# CableUndefinedMini_Rev2.net
KiCad netlist of a schematic drawn in EasyEDA
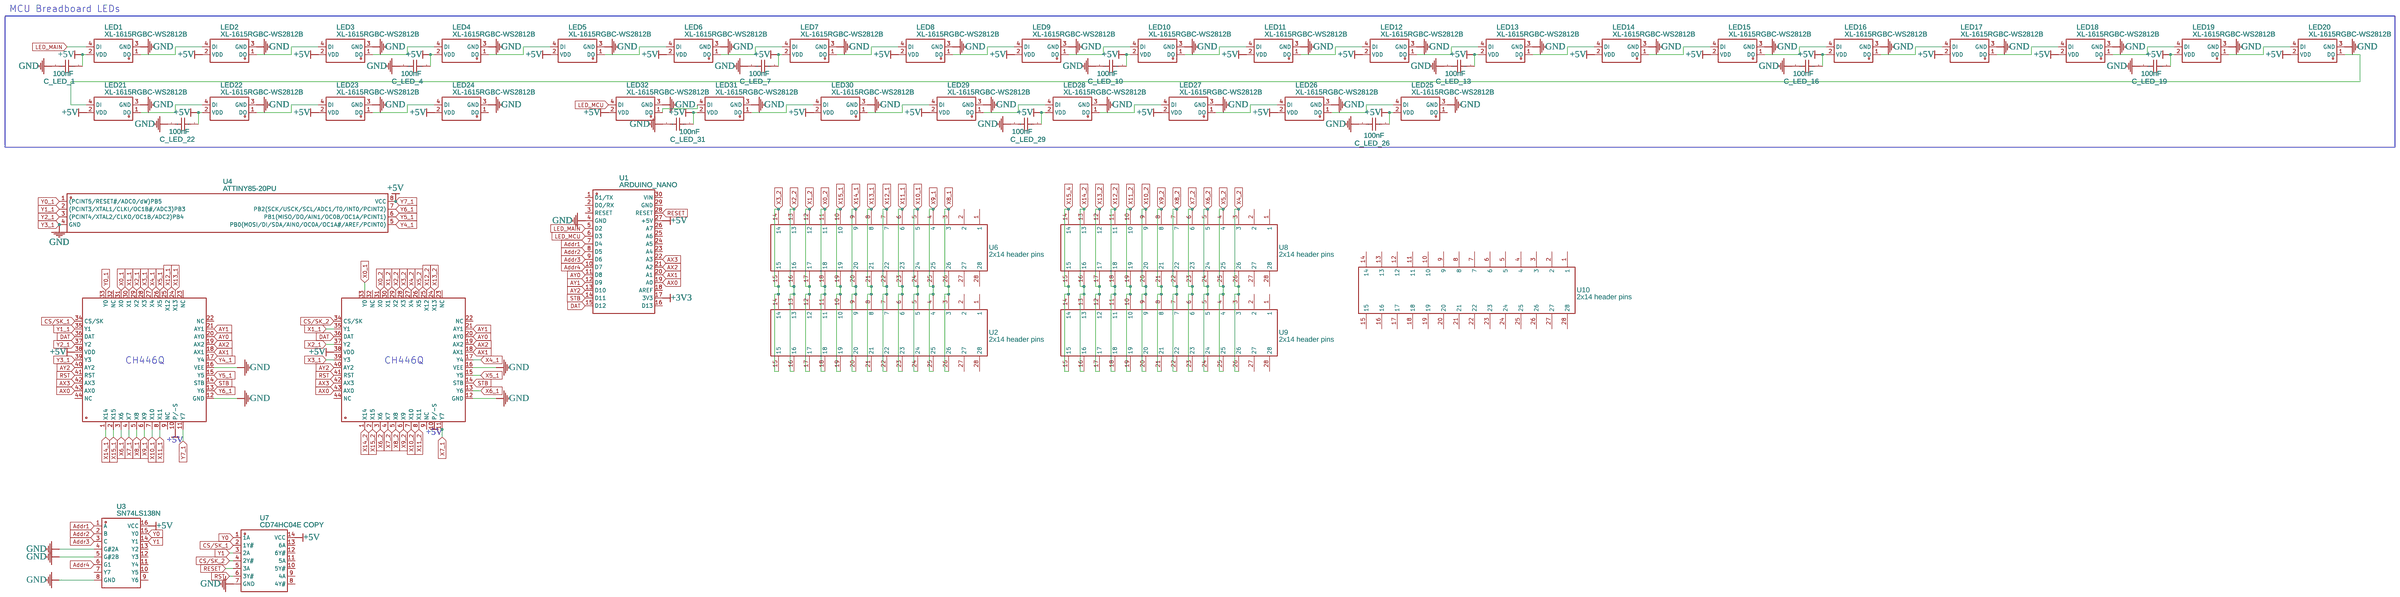
[diagram p0: schematic sheet]

(export (version "E")
  (design (tool "Eeschema 10.0.6"))
  (components
    (comp (ref "C_LED_1")
      (value "100nF")
      (fields
        (field (name "Manufacturer Part") "AC0402KRX7R9BB104")
        (field (name "Manufacturer") "YAGEO(国巨)")
      )
      (libsource (lib "") (part "AC0402KRX7R9BB104"))
    )
    (comp (ref "C_LED_4")
      (value "100nF")
      (fields
        (field (name "Manufacturer Part") "AC0402KRX7R9BB104")
        (field (name "Manufacturer") "YAGEO(国巨)")
      )
      (libsource (lib "") (part "AC0402KRX7R9BB104"))
    )
    (comp (ref "C_LED_7")
      (value "100nF")
      (fields
        (field (name "Manufacturer Part") "AC0402KRX7R9BB104")
        (field (name "Manufacturer") "YAGEO(国巨)")
      )
      (libsource (lib "") (part "AC0402KRX7R9BB104"))
    )
    (comp (ref "C_LED_10")
      (value "100nF")
      (fields
        (field (name "Manufacturer Part") "AC0402KRX7R9BB104")
        (field (name "Manufacturer") "YAGEO(国巨)")
      )
      (libsource (lib "") (part "AC0402KRX7R9BB104"))
    )
    (comp (ref "C_LED_13")
      (value "100nF")
      (fields
        (field (name "Manufacturer Part") "AC0402KRX7R9BB104")
        (field (name "Manufacturer") "YAGEO(国巨)")
      )
      (libsource (lib "") (part "AC0402KRX7R9BB104"))
    )
    (comp (ref "C_LED_16")
      (value "100nF")
      (fields
        (field (name "Manufacturer Part") "AC0402KRX7R9BB104")
        (field (name "Manufacturer") "YAGEO(国巨)")
      )
      (libsource (lib "") (part "AC0402KRX7R9BB104"))
    )
    (comp (ref "C_LED_19")
      (value "100nF")
      (fields
        (field (name "Manufacturer Part") "AC0402KRX7R9BB104")
        (field (name "Manufacturer") "YAGEO(国巨)")
      )
      (libsource (lib "") (part "AC0402KRX7R9BB104"))
    )
    (comp (ref "C_LED_22")
      (value "100nF")
      (fields
        (field (name "Manufacturer Part") "AC0402KRX7R9BB104")
        (field (name "Manufacturer") "YAGEO(国巨)")
      )
      (libsource (lib "") (part "AC0402KRX7R9BB104"))
    )
    (comp (ref "C_LED_26")
      (value "100nF")
      (fields
        (field (name "Manufacturer Part") "AC0402KRX7R9BB104")
        (field (name "Manufacturer") "YAGEO(国巨)")
      )
      (libsource (lib "") (part "AC0402KRX7R9BB104"))
    )
    (comp (ref "C_LED_29")
      (value "100nF")
      (fields
        (field (name "Manufacturer Part") "AC0402KRX7R9BB104")
        (field (name "Manufacturer") "YAGEO(国巨)")
      )
      (libsource (lib "") (part "AC0402KRX7R9BB104"))
    )
    (comp (ref "C_LED_31")
      (value "100nF")
      (fields
        (field (name "Manufacturer Part") "AC0402KRX7R9BB104")
        (field (name "Manufacturer") "YAGEO(国巨)")
      )
      (libsource (lib "") (part "AC0402KRX7R9BB104"))
    )
    (comp (ref "LED1")
      (value "XL-1615RGBC-WS2812B")
      (fields (field (name "Manufacturer") "XINGLIGHT(成兴光)"))
      (libsource (lib "") (part "XL-1615RGBC-WS2812B"))
    )
    (comp (ref "LED2")
      (value "XL-1615RGBC-WS2812B")
      (fields (field (name "Manufacturer") "XINGLIGHT(成兴光)"))
      (libsource (lib "") (part "XL-1615RGBC-WS2812B"))
    )
    (comp (ref "LED3")
      (value "XL-1615RGBC-WS2812B")
      (fields (field (name "Manufacturer") "XINGLIGHT(成兴光)"))
      (libsource (lib "") (part "XL-1615RGBC-WS2812B"))
    )
    (comp (ref "LED4")
      (value "XL-1615RGBC-WS2812B")
      (fields (field (name "Manufacturer") "XINGLIGHT(成兴光)"))
      (libsource (lib "") (part "XL-1615RGBC-WS2812B"))
    )
    (comp (ref "LED5")
      (value "XL-1615RGBC-WS2812B")
      (fields (field (name "Manufacturer") "XINGLIGHT(成兴光)"))
      (libsource (lib "") (part "XL-1615RGBC-WS2812B"))
    )
    (comp (ref "LED6")
      (value "XL-1615RGBC-WS2812B")
      (fields (field (name "Manufacturer") "XINGLIGHT(成兴光)"))
      (libsource (lib "") (part "XL-1615RGBC-WS2812B"))
    )
    (comp (ref "LED7")
      (value "XL-1615RGBC-WS2812B")
      (fields (field (name "Manufacturer") "XINGLIGHT(成兴光)"))
      (libsource (lib "") (part "XL-1615RGBC-WS2812B"))
    )
    (comp (ref "LED8")
      (value "XL-1615RGBC-WS2812B")
      (fields (field (name "Manufacturer") "XINGLIGHT(成兴光)"))
      (libsource (lib "") (part "XL-1615RGBC-WS2812B"))
    )
    (comp (ref "LED9")
      (value "XL-1615RGBC-WS2812B")
      (fields (field (name "Manufacturer") "XINGLIGHT(成兴光)"))
      (libsource (lib "") (part "XL-1615RGBC-WS2812B"))
    )
    (comp (ref "LED10")
      (value "XL-1615RGBC-WS2812B")
      (fields (field (name "Manufacturer") "XINGLIGHT(成兴光)"))
      (libsource (lib "") (part "XL-1615RGBC-WS2812B"))
    )
    (comp (ref "LED11")
      (value "XL-1615RGBC-WS2812B")
      (fields (field (name "Manufacturer") "XINGLIGHT(成兴光)"))
      (libsource (lib "") (part "XL-1615RGBC-WS2812B"))
    )
    (comp (ref "LED12")
      (value "XL-1615RGBC-WS2812B")
      (fields (field (name "Manufacturer") "XINGLIGHT(成兴光)"))
      (libsource (lib "") (part "XL-1615RGBC-WS2812B"))
    )
    (comp (ref "LED13")
      (value "XL-1615RGBC-WS2812B")
      (fields (field (name "Manufacturer") "XINGLIGHT(成兴光)"))
      (libsource (lib "") (part "XL-1615RGBC-WS2812B"))
    )
    (comp (ref "LED14")
      (value "XL-1615RGBC-WS2812B")
      (fields (field (name "Manufacturer") "XINGLIGHT(成兴光)"))
      (libsource (lib "") (part "XL-1615RGBC-WS2812B"))
    )
    (comp (ref "LED15")
      (value "XL-1615RGBC-WS2812B")
      (fields (field (name "Manufacturer") "XINGLIGHT(成兴光)"))
      (libsource (lib "") (part "XL-1615RGBC-WS2812B"))
    )
    (comp (ref "LED16")
      (value "XL-1615RGBC-WS2812B")
      (fields (field (name "Manufacturer") "XINGLIGHT(成兴光)"))
      (libsource (lib "") (part "XL-1615RGBC-WS2812B"))
    )
    (comp (ref "LED17")
      (value "XL-1615RGBC-WS2812B")
      (fields (field (name "Manufacturer") "XINGLIGHT(成兴光)"))
      (libsource (lib "") (part "XL-1615RGBC-WS2812B"))
    )
    (comp (ref "LED18")
      (value "XL-1615RGBC-WS2812B")
      (fields (field (name "Manufacturer") "XINGLIGHT(成兴光)"))
      (libsource (lib "") (part "XL-1615RGBC-WS2812B"))
    )
    (comp (ref "LED19")
      (value "XL-1615RGBC-WS2812B")
      (fields (field (name "Manufacturer") "XINGLIGHT(成兴光)"))
      (libsource (lib "") (part "XL-1615RGBC-WS2812B"))
    )
    (comp (ref "LED20")
      (value "XL-1615RGBC-WS2812B")
      (fields (field (name "Manufacturer") "XINGLIGHT(成兴光)"))
      (libsource (lib "") (part "XL-1615RGBC-WS2812B"))
    )
    (comp (ref "LED21")
      (value "XL-1615RGBC-WS2812B")
      (fields (field (name "Manufacturer") "XINGLIGHT(成兴光)"))
      (libsource (lib "") (part "XL-1615RGBC-WS2812B"))
    )
    (comp (ref "LED22")
      (value "XL-1615RGBC-WS2812B")
      (fields (field (name "Manufacturer") "XINGLIGHT(成兴光)"))
      (libsource (lib "") (part "XL-1615RGBC-WS2812B"))
    )
    (comp (ref "LED23")
      (value "XL-1615RGBC-WS2812B")
      (fields (field (name "Manufacturer") "XINGLIGHT(成兴光)"))
      (libsource (lib "") (part "XL-1615RGBC-WS2812B"))
    )
    (comp (ref "LED24")
      (value "XL-1615RGBC-WS2812B")
      (fields (field (name "Manufacturer") "XINGLIGHT(成兴光)"))
      (libsource (lib "") (part "XL-1615RGBC-WS2812B"))
    )
    (comp (ref "LED25")
      (value "XL-1615RGBC-WS2812B")
      (fields (field (name "Manufacturer") "XINGLIGHT(成兴光)"))
      (libsource (lib "") (part "XL-1615RGBC-WS2812B"))
    )
    (comp (ref "LED26")
      (value "XL-1615RGBC-WS2812B")
      (fields (field (name "Manufacturer") "XINGLIGHT(成兴光)"))
      (libsource (lib "") (part "XL-1615RGBC-WS2812B"))
    )
    (comp (ref "LED27")
      (value "XL-1615RGBC-WS2812B")
      (fields (field (name "Manufacturer") "XINGLIGHT(成兴光)"))
      (libsource (lib "") (part "XL-1615RGBC-WS2812B"))
    )
    (comp (ref "LED28")
      (value "XL-1615RGBC-WS2812B")
      (fields (field (name "Manufacturer") "XINGLIGHT(成兴光)"))
      (libsource (lib "") (part "XL-1615RGBC-WS2812B"))
    )
    (comp (ref "LED29")
      (value "XL-1615RGBC-WS2812B")
      (fields (field (name "Manufacturer") "XINGLIGHT(成兴光)"))
      (libsource (lib "") (part "XL-1615RGBC-WS2812B"))
    )
    (comp (ref "LED30")
      (value "XL-1615RGBC-WS2812B")
      (fields (field (name "Manufacturer") "XINGLIGHT(成兴光)"))
      (libsource (lib "") (part "XL-1615RGBC-WS2812B"))
    )
    (comp (ref "LED31")
      (value "XL-1615RGBC-WS2812B")
      (fields (field (name "Manufacturer") "XINGLIGHT(成兴光)"))
      (libsource (lib "") (part "XL-1615RGBC-WS2812B"))
    )
    (comp (ref "LED32")
      (value "XL-1615RGBC-WS2812B")
      (fields (field (name "Manufacturer") "XINGLIGHT(成兴光)"))
      (libsource (lib "") (part "XL-1615RGBC-WS2812B"))
    )
    (comp (ref "M1")
      (value "CH446Q")
      (fields (field (name "Manufacturer") "WCH(南京沁恒)"))
      (libsource (lib "") (part "CH446Q"))
    )
    (comp (ref "M2")
      (value "CH446Q")
      (fields (field (name "Manufacturer") "WCH(南京沁恒)"))
      (libsource (lib "") (part "CH446Q"))
    )
    (comp (ref "U1") (value "ARDUINO_NANO") (libsource (lib "") (part "ARDUINO_NANO")))
    (comp (ref "U2") (value "2x14 header pins") (libsource (lib "") (part "2x14 header pins")))
    (comp (ref "U3")
      (value "SN74LS138N")
      (fields (field (name "Manufacturer") "TI(德州仪器)"))
      (libsource (lib "") (part "SN74LS138N"))
    )
    (comp (ref "U4")
      (value "ATTINY85-20PU")
      (fields (field (name "Manufacturer") "MICROCHIP(美国微芯)"))
      (libsource (lib "") (part "ATTINY85-20PU"))
    )
    (comp (ref "U6") (value "2x14 header pins") (libsource (lib "") (part "2x14 header pins")))
    (comp (ref "U7")
      (value "CD74HC04E COPY")
      (fields
        (field (name "Manufacturer Part") "CD74HC04E")
        (field (name "Manufacturer") "Texas Instruments")
      )
      (libsource (lib "") (part "CD74HC04E COPY"))
    )
    (comp (ref "U8") (value "2x14 header pins") (libsource (lib "") (part "2x14 header pins")))
    (comp (ref "U9") (value "2x14 header pins") (libsource (lib "") (part "2x14 header pins")))
    (comp (ref "U10") (value "2x14 header pins") (libsource (lib "") (part "2x14 header pins")))
  )
  (nets
    (net (code "1") (name "+3V3") (class "Default")
      (node (ref "U1") (pin "17") (pinfunction "3V3_17") (pintype "unspecified"))
    )
    (net (code "2") (name "AX0") (class "Default")
      (node (ref "M1") (pin "43") (pinfunction "AX0_43") (pintype "unspecified"))
      (node (ref "M2") (pin "43") (pinfunction "AX0_43") (pintype "unspecified"))
      (node (ref "U1") (pin "19") (pinfunction "A0_19") (pintype "unspecified"))
    )
    (net (code "3") (name "AX1") (class "Default")
      (node (ref "M1") (pin "18") (pinfunction "AX1_18") (pintype "unspecified"))
      (node (ref "M2") (pin "18") (pinfunction "AX1_18") (pintype "unspecified"))
      (node (ref "U1") (pin "20") (pinfunction "A1_20") (pintype "unspecified"))
    )
    (net (code "4") (name "AX2") (class "Default")
      (node (ref "M1") (pin "19") (pinfunction "AX2_19") (pintype "unspecified"))
      (node (ref "M2") (pin "19") (pinfunction "AX2_19") (pintype "unspecified"))
      (node (ref "U1") (pin "21") (pinfunction "A2_21") (pintype "unspecified"))
    )
    (net (code "5") (name "AX3") (class "Default")
      (node (ref "M1") (pin "42") (pinfunction "AX3_42") (pintype "unspecified"))
      (node (ref "M2") (pin "42") (pinfunction "AX3_42") (pintype "unspecified"))
      (node (ref "U1") (pin "22") (pinfunction "A3_22") (pintype "unspecified"))
    )
    (net (code "6") (name "AY0") (class "Default")
      (node (ref "M1") (pin "20") (pinfunction "AY0_20") (pintype "unspecified"))
      (node (ref "M2") (pin "20") (pinfunction "AY0_20") (pintype "unspecified"))
      (node (ref "U1") (pin "11") (pinfunction "D8_11") (pintype "unspecified"))
    )
    (net (code "7") (name "AY1") (class "Default")
      (node (ref "M1") (pin "21") (pinfunction "AY1_21") (pintype "unspecified"))
      (node (ref "M2") (pin "21") (pinfunction "AY1_21") (pintype "unspecified"))
      (node (ref "U1") (pin "12") (pinfunction "D9_12") (pintype "unspecified"))
    )
    (net (code "8") (name "AY2") (class "Default")
      (node (ref "M1") (pin "40") (pinfunction "AY2_40") (pintype "unspecified"))
      (node (ref "M2") (pin "40") (pinfunction "AY2_40") (pintype "unspecified"))
      (node (ref "U1") (pin "13") (pinfunction "D10_13") (pintype "unspecified"))
    )
    (net (code "9") (name "Addr1") (class "Default")
      (node (ref "U1") (pin "7") (pinfunction "D4_7") (pintype "unspecified"))
      (node (ref "U3") (pin "1") (pinfunction "A_1") (pintype "unspecified"))
    )
    (net (code "10") (name "Addr2") (class "Default")
      (node (ref "U1") (pin "8") (pinfunction "D5_8") (pintype "unspecified"))
      (node (ref "U3") (pin "2") (pinfunction "B_2") (pintype "unspecified"))
    )
    (net (code "11") (name "Addr3") (class "Default")
      (node (ref "U1") (pin "9") (pinfunction "D6_9") (pintype "unspecified"))
      (node (ref "U3") (pin "3") (pinfunction "C_3") (pintype "unspecified"))
    )
    (net (code "12") (name "Addr4") (class "Default")
      (node (ref "U1") (pin "10") (pinfunction "D7_10") (pintype "unspecified"))
      (node (ref "U3") (pin "6") (pinfunction "G1_6") (pintype "unspecified"))
    )
    (net (code "13") (name "CS{slash}SK_1") (class "Default")
      (node (ref "M1") (pin "34") (pinfunction "CS/SK_34") (pintype "unspecified"))
      (node (ref "U7") (pin "2") (pinfunction "1Y#_2") (pintype "unspecified"))
    )
    (net (code "14") (name "CS{slash}SK_2") (class "Default")
      (node (ref "M2") (pin "34") (pinfunction "CS/SK_34") (pintype "unspecified"))
      (node (ref "U7") (pin "4") (pinfunction "2Y#_4") (pintype "unspecified"))
    )
    (net (code "15") (name "DAT") (class "Default")
      (node (ref "M1") (pin "36") (pinfunction "DAT_36") (pintype "unspecified"))
      (node (ref "M2") (pin "36") (pinfunction "DAT_36") (pintype "unspecified"))
      (node (ref "U1") (pin "15") (pinfunction "D12_15") (pintype "unspecified"))
    )
    (net (code "16") (name "LED_MAIN") (class "Default")
      (node (ref "LED1") (pin "4") (pinfunction "DI_4") (pintype "unspecified"))
      (node (ref "U1") (pin "5") (pinfunction "D2_5") (pintype "unspecified"))
    )
    (net (code "17") (name "LED_MCU") (class "Default")
      (node (ref "LED32") (pin "4") (pinfunction "DI_4") (pintype "unspecified"))
      (node (ref "U1") (pin "6") (pinfunction "D3_6") (pintype "unspecified"))
    )
    (net (code "18") (name "Net-(LED1-DO)") (class "Default")
      (node (ref "LED1") (pin "1") (pinfunction "DO_1") (pintype "unspecified"))
      (node (ref "LED2") (pin "4") (pinfunction "DI_4") (pintype "unspecified"))
    )
    (net (code "19") (name "Net-(LED2-DO)") (class "Default")
      (node (ref "LED2") (pin "1") (pinfunction "DO_1") (pintype "unspecified"))
      (node (ref "LED3") (pin "4") (pinfunction "DI_4") (pintype "unspecified"))
    )
    (net (code "20") (name "Net-(LED3-DO)") (class "Default")
      (node (ref "LED3") (pin "1") (pinfunction "DO_1") (pintype "unspecified"))
      (node (ref "LED4") (pin "4") (pinfunction "DI_4") (pintype "unspecified"))
    )
    (net (code "21") (name "Net-(LED4-DO)") (class "Default")
      (node (ref "LED4") (pin "1") (pinfunction "DO_1") (pintype "unspecified"))
      (node (ref "LED5") (pin "4") (pinfunction "DI_4") (pintype "unspecified"))
    )
    (net (code "22") (name "Net-(LED5-DO)") (class "Default")
      (node (ref "LED5") (pin "1") (pinfunction "DO_1") (pintype "unspecified"))
      (node (ref "LED6") (pin "4") (pinfunction "DI_4") (pintype "unspecified"))
    )
    (net (code "23") (name "Net-(LED6-DO)") (class "Default")
      (node (ref "LED6") (pin "1") (pinfunction "DO_1") (pintype "unspecified"))
      (node (ref "LED7") (pin "4") (pinfunction "DI_4") (pintype "unspecified"))
    )
    (net (code "24") (name "Net-(LED7-DO)") (class "Default")
      (node (ref "LED7") (pin "1") (pinfunction "DO_1") (pintype "unspecified"))
      (node (ref "LED8") (pin "4") (pinfunction "DI_4") (pintype "unspecified"))
    )
    (net (code "25") (name "Net-(LED8-DO)") (class "Default")
      (node (ref "LED8") (pin "1") (pinfunction "DO_1") (pintype "unspecified"))
      (node (ref "LED9") (pin "4") (pinfunction "DI_4") (pintype "unspecified"))
    )
    (net (code "26") (name "Net-(LED10-DI)") (class "Default")
      (node (ref "LED10") (pin "4") (pinfunction "DI_4") (pintype "unspecified"))
      (node (ref "LED9") (pin "1") (pinfunction "DO_1") (pintype "unspecified"))
    )
    (net (code "27") (name "Net-(LED10-DO)") (class "Default")
      (node (ref "LED10") (pin "1") (pinfunction "DO_1") (pintype "unspecified"))
      (node (ref "LED11") (pin "4") (pinfunction "DI_4") (pintype "unspecified"))
    )
    (net (code "28") (name "Net-(LED11-DO)") (class "Default")
      (node (ref "LED11") (pin "1") (pinfunction "DO_1") (pintype "unspecified"))
      (node (ref "LED12") (pin "4") (pinfunction "DI_4") (pintype "unspecified"))
    )
    (net (code "29") (name "Net-(LED12-DO)") (class "Default")
      (node (ref "LED12") (pin "1") (pinfunction "DO_1") (pintype "unspecified"))
      (node (ref "LED13") (pin "4") (pinfunction "DI_4") (pintype "unspecified"))
    )
    (net (code "30") (name "Net-(LED13-DO)") (class "Default")
      (node (ref "LED13") (pin "1") (pinfunction "DO_1") (pintype "unspecified"))
      (node (ref "LED14") (pin "4") (pinfunction "DI_4") (pintype "unspecified"))
    )
    (net (code "31") (name "Net-(LED14-DO)") (class "Default")
      (node (ref "LED14") (pin "1") (pinfunction "DO_1") (pintype "unspecified"))
      (node (ref "LED15") (pin "4") (pinfunction "DI_4") (pintype "unspecified"))
    )
    (net (code "32") (name "Net-(LED15-DO)") (class "Default")
      (node (ref "LED15") (pin "1") (pinfunction "DO_1") (pintype "unspecified"))
      (node (ref "LED16") (pin "4") (pinfunction "DI_4") (pintype "unspecified"))
    )
    (net (code "33") (name "Net-(LED16-DO)") (class "Default")
      (node (ref "LED16") (pin "1") (pinfunction "DO_1") (pintype "unspecified"))
      (node (ref "LED17") (pin "4") (pinfunction "DI_4") (pintype "unspecified"))
    )
    (net (code "34") (name "Net-(LED17-DO)") (class "Default")
      (node (ref "LED17") (pin "1") (pinfunction "DO_1") (pintype "unspecified"))
      (node (ref "LED18") (pin "4") (pinfunction "DI_4") (pintype "unspecified"))
    )
    (net (code "35") (name "Net-(LED18-DO)") (class "Default")
      (node (ref "LED18") (pin "1") (pinfunction "DO_1") (pintype "unspecified"))
      (node (ref "LED19") (pin "4") (pinfunction "DI_4") (pintype "unspecified"))
    )
    (net (code "36") (name "Net-(LED19-DO)") (class "Default")
      (node (ref "LED19") (pin "1") (pinfunction "DO_1") (pintype "unspecified"))
      (node (ref "LED20") (pin "4") (pinfunction "DI_4") (pintype "unspecified"))
    )
    (net (code "37") (name "Net-(LED20-DO)") (class "Default")
      (node (ref "LED20") (pin "1") (pinfunction "DO_1") (pintype "unspecified"))
      (node (ref "LED21") (pin "4") (pinfunction "DI_4") (pintype "unspecified"))
    )
    (net (code "38") (name "Net-(LED21-DO)") (class "Default")
      (node (ref "LED21") (pin "1") (pinfunction "DO_1") (pintype "unspecified"))
      (node (ref "LED22") (pin "4") (pinfunction "DI_4") (pintype "unspecified"))
    )
    (net (code "39") (name "Net-(LED22-DO)") (class "Default")
      (node (ref "LED22") (pin "1") (pinfunction "DO_1") (pintype "unspecified"))
      (node (ref "LED23") (pin "4") (pinfunction "DI_4") (pintype "unspecified"))
    )
    (net (code "40") (name "Net-(LED23-DO)") (class "Default")
      (node (ref "LED23") (pin "1") (pinfunction "DO_1") (pintype "unspecified"))
      (node (ref "LED24") (pin "4") (pinfunction "DI_4") (pintype "unspecified"))
    )
    (net (code "41") (name "Net-(LED25-DI)") (class "Default")
      (node (ref "LED25") (pin "4") (pinfunction "DI_4") (pintype "unspecified"))
      (node (ref "LED26") (pin "1") (pinfunction "DO_1") (pintype "unspecified"))
    )
    (net (code "42") (name "Net-(LED26-DI)") (class "Default")
      (node (ref "LED26") (pin "4") (pinfunction "DI_4") (pintype "unspecified"))
      (node (ref "LED27") (pin "1") (pinfunction "DO_1") (pintype "unspecified"))
    )
    (net (code "43") (name "Net-(LED27-DI)") (class "Default")
      (node (ref "LED27") (pin "4") (pinfunction "DI_4") (pintype "unspecified"))
      (node (ref "LED28") (pin "1") (pinfunction "DO_1") (pintype "unspecified"))
    )
    (net (code "44") (name "Net-(LED28-DI)") (class "Default")
      (node (ref "LED28") (pin "4") (pinfunction "DI_4") (pintype "unspecified"))
      (node (ref "LED29") (pin "1") (pinfunction "DO_1") (pintype "unspecified"))
    )
    (net (code "45") (name "Net-(LED29-DI)") (class "Default")
      (node (ref "LED29") (pin "4") (pinfunction "DI_4") (pintype "unspecified"))
      (node (ref "LED30") (pin "1") (pinfunction "DO_1") (pintype "unspecified"))
    )
    (net (code "46") (name "Net-(LED30-DI)") (class "Default")
      (node (ref "LED30") (pin "4") (pinfunction "DI_4") (pintype "unspecified"))
      (node (ref "LED31") (pin "1") (pinfunction "DO_1") (pintype "unspecified"))
    )
    (net (code "47") (name "Net-(LED31-DI)") (class "Default")
      (node (ref "LED31") (pin "4") (pinfunction "DI_4") (pintype "unspecified"))
      (node (ref "LED32") (pin "1") (pinfunction "DO_1") (pintype "unspecified"))
    )
    (net (code "48") (name "RESET") (class "Default")
      (node (ref "U1") (pin "28") (pinfunction "RESET_28") (pintype "unspecified"))
      (node (ref "U7") (pin "5") (pinfunction "3A_5") (pintype "unspecified"))
    )
    (net (code "49") (name "RST") (class "Default")
      (node (ref "M1") (pin "41") (pinfunction "RST_41") (pintype "unspecified"))
      (node (ref "M2") (pin "41") (pinfunction "RST_41") (pintype "unspecified"))
      (node (ref "U7") (pin "6") (pinfunction "3Y#_6") (pintype "unspecified"))
    )
    (net (code "50") (name "STB") (class "Default")
      (node (ref "M1") (pin "14") (pinfunction "STB_14") (pintype "unspecified"))
      (node (ref "M2") (pin "14") (pinfunction "STB_14") (pintype "unspecified"))
      (node (ref "U1") (pin "14") (pinfunction "D11_14") (pintype "unspecified"))
    )
    (net (code "51") (name "X0_1") (class "Default")
      (node (ref "M1") (pin "31") (pinfunction "X0_31") (pintype "unspecified"))
      (node (ref "M2") (pin "33") (pinfunction "Y0_33") (pintype "unspecified"))
    )
    (net (code "52") (name "X0_2") (class "Default")
      (node (ref "M2") (pin "31") (pinfunction "X0_31") (pintype "unspecified"))
      (node (ref "U2") (pin "11") (pinfunction "11_11") (pintype "unspecified"))
      (node (ref "U2") (pin "18") (pinfunction "18_18") (pintype "unspecified"))
      (node (ref "U6") (pin "11") (pinfunction "11_11") (pintype "unspecified"))
      (node (ref "U6") (pin "18") (pinfunction "18_18") (pintype "unspecified"))
    )
    (net (code "53") (name "X1_1") (class "Default")
      (node (ref "M1") (pin "30") (pinfunction "X1_30") (pintype "unspecified"))
      (node (ref "M2") (pin "35") (pinfunction "Y1_35") (pintype "unspecified"))
    )
    (net (code "54") (name "X1_2") (class "Default")
      (node (ref "M2") (pin "30") (pinfunction "X1_30") (pintype "unspecified"))
      (node (ref "U2") (pin "12") (pinfunction "12_12") (pintype "unspecified"))
      (node (ref "U2") (pin "17") (pinfunction "17_17") (pintype "unspecified"))
      (node (ref "U6") (pin "12") (pinfunction "12_12") (pintype "unspecified"))
      (node (ref "U6") (pin "17") (pinfunction "17_17") (pintype "unspecified"))
    )
    (net (code "55") (name "X2_1") (class "Default")
      (node (ref "M1") (pin "29") (pinfunction "X2_29") (pintype "unspecified"))
      (node (ref "M2") (pin "37") (pinfunction "Y2_37") (pintype "unspecified"))
    )
    (net (code "56") (name "X2_2") (class "Default")
      (node (ref "M2") (pin "29") (pinfunction "X2_29") (pintype "unspecified"))
      (node (ref "U2") (pin "13") (pinfunction "13_13") (pintype "unspecified"))
      (node (ref "U2") (pin "16") (pinfunction "16_16") (pintype "unspecified"))
      (node (ref "U6") (pin "13") (pinfunction "13_13") (pintype "unspecified"))
      (node (ref "U6") (pin "16") (pinfunction "16_16") (pintype "unspecified"))
    )
    (net (code "57") (name "X3_1") (class "Default")
      (node (ref "M1") (pin "28") (pinfunction "X3_28") (pintype "unspecified"))
      (node (ref "M2") (pin "39") (pinfunction "Y3_39") (pintype "unspecified"))
    )
    (net (code "58") (name "X3_2") (class "Default")
      (node (ref "M2") (pin "28") (pinfunction "X3_28") (pintype "unspecified"))
      (node (ref "U2") (pin "14") (pinfunction "14_14") (pintype "unspecified"))
      (node (ref "U2") (pin "15") (pinfunction "15_15") (pintype "unspecified"))
      (node (ref "U6") (pin "14") (pinfunction "14_14") (pintype "unspecified"))
      (node (ref "U6") (pin "15") (pinfunction "15_15") (pintype "unspecified"))
    )
    (net (code "59") (name "X4_1") (class "Default")
      (node (ref "M1") (pin "27") (pinfunction "X4_27") (pintype "unspecified"))
      (node (ref "M2") (pin "17") (pinfunction "Y4_17") (pintype "unspecified"))
    )
    (net (code "60") (name "X4_2") (class "Default")
      (node (ref "M2") (pin "27") (pinfunction "X4_27") (pintype "unspecified"))
      (node (ref "U8") (pin "26") (pinfunction "26_26") (pintype "unspecified"))
      (node (ref "U8") (pin "3") (pinfunction "3_3") (pintype "unspecified"))
      (node (ref "U9") (pin "26") (pinfunction "26_26") (pintype "unspecified"))
      (node (ref "U9") (pin "3") (pinfunction "3_3") (pintype "unspecified"))
    )
    (net (code "61") (name "X5_1") (class "Default")
      (node (ref "M1") (pin "26") (pinfunction "X5_26") (pintype "unspecified"))
      (node (ref "M2") (pin "15") (pinfunction "Y5_15") (pintype "unspecified"))
    )
    (net (code "62") (name "X5_2") (class "Default")
      (node (ref "M2") (pin "26") (pinfunction "X5_26") (pintype "unspecified"))
      (node (ref "U8") (pin "25") (pinfunction "25_25") (pintype "unspecified"))
      (node (ref "U8") (pin "4") (pinfunction "4_4") (pintype "unspecified"))
      (node (ref "U9") (pin "25") (pinfunction "25_25") (pintype "unspecified"))
      (node (ref "U9") (pin "4") (pinfunction "4_4") (pintype "unspecified"))
    )
    (net (code "63") (name "X6_1") (class "Default")
      (node (ref "M1") (pin "3") (pinfunction "X6_3") (pintype "unspecified"))
      (node (ref "M2") (pin "13") (pinfunction "Y6_13") (pintype "unspecified"))
    )
    (net (code "64") (name "X6_2") (class "Default")
      (node (ref "M2") (pin "3") (pinfunction "X6_3") (pintype "unspecified"))
      (node (ref "U8") (pin "24") (pinfunction "24_24") (pintype "unspecified"))
      (node (ref "U8") (pin "5") (pinfunction "5_5") (pintype "unspecified"))
      (node (ref "U9") (pin "24") (pinfunction "24_24") (pintype "unspecified"))
      (node (ref "U9") (pin "5") (pinfunction "5_5") (pintype "unspecified"))
    )
    (net (code "65") (name "X7_1") (class "Default")
      (node (ref "M1") (pin "4") (pinfunction "X7_4") (pintype "unspecified"))
      (node (ref "M2") (pin "11") (pinfunction "Y7_11") (pintype "unspecified"))
    )
    (net (code "66") (name "X7_2") (class "Default")
      (node (ref "M2") (pin "4") (pinfunction "X7_4") (pintype "unspecified"))
      (node (ref "U8") (pin "23") (pinfunction "23_23") (pintype "unspecified"))
      (node (ref "U8") (pin "6") (pinfunction "6_6") (pintype "unspecified"))
      (node (ref "U9") (pin "23") (pinfunction "23_23") (pintype "unspecified"))
      (node (ref "U9") (pin "6") (pinfunction "6_6") (pintype "unspecified"))
    )
    (net (code "67") (name "X8_1") (class "Default")
      (node (ref "M1") (pin "5") (pinfunction "X8_5") (pintype "unspecified"))
      (node (ref "U2") (pin "26") (pinfunction "26_26") (pintype "unspecified"))
      (node (ref "U2") (pin "3") (pinfunction "3_3") (pintype "unspecified"))
      (node (ref "U6") (pin "26") (pinfunction "26_26") (pintype "unspecified"))
      (node (ref "U6") (pin "3") (pinfunction "3_3") (pintype "unspecified"))
    )
    (net (code "68") (name "X8_2") (class "Default")
      (node (ref "M2") (pin "5") (pinfunction "X8_5") (pintype "unspecified"))
      (node (ref "U8") (pin "22") (pinfunction "22_22") (pintype "unspecified"))
      (node (ref "U8") (pin "7") (pinfunction "7_7") (pintype "unspecified"))
      (node (ref "U9") (pin "22") (pinfunction "22_22") (pintype "unspecified"))
      (node (ref "U9") (pin "7") (pinfunction "7_7") (pintype "unspecified"))
    )
    (net (code "69") (name "X9_1") (class "Default")
      (node (ref "M1") (pin "6") (pinfunction "X9_6") (pintype "unspecified"))
      (node (ref "U2") (pin "25") (pinfunction "25_25") (pintype "unspecified"))
      (node (ref "U2") (pin "4") (pinfunction "4_4") (pintype "unspecified"))
      (node (ref "U6") (pin "25") (pinfunction "25_25") (pintype "unspecified"))
      (node (ref "U6") (pin "4") (pinfunction "4_4") (pintype "unspecified"))
    )
    (net (code "70") (name "X9_2") (class "Default")
      (node (ref "M2") (pin "6") (pinfunction "X9_6") (pintype "unspecified"))
      (node (ref "U8") (pin "21") (pinfunction "21_21") (pintype "unspecified"))
      (node (ref "U8") (pin "8") (pinfunction "8_8") (pintype "unspecified"))
      (node (ref "U9") (pin "21") (pinfunction "21_21") (pintype "unspecified"))
      (node (ref "U9") (pin "8") (pinfunction "8_8") (pintype "unspecified"))
    )
    (net (code "71") (name "X10_1") (class "Default")
      (node (ref "M1") (pin "7") (pinfunction "X10_7") (pintype "unspecified"))
      (node (ref "U2") (pin "24") (pinfunction "24_24") (pintype "unspecified"))
      (node (ref "U2") (pin "5") (pinfunction "5_5") (pintype "unspecified"))
      (node (ref "U6") (pin "24") (pinfunction "24_24") (pintype "unspecified"))
      (node (ref "U6") (pin "5") (pinfunction "5_5") (pintype "unspecified"))
    )
    (net (code "72") (name "X10_2") (class "Default")
      (node (ref "M2") (pin "7") (pinfunction "X10_7") (pintype "unspecified"))
      (node (ref "U8") (pin "20") (pinfunction "20_20") (pintype "unspecified"))
      (node (ref "U8") (pin "9") (pinfunction "9_9") (pintype "unspecified"))
      (node (ref "U9") (pin "20") (pinfunction "20_20") (pintype "unspecified"))
      (node (ref "U9") (pin "9") (pinfunction "9_9") (pintype "unspecified"))
    )
    (net (code "73") (name "X11_1") (class "Default")
      (node (ref "M1") (pin "8") (pinfunction "X11_8") (pintype "unspecified"))
      (node (ref "U2") (pin "23") (pinfunction "23_23") (pintype "unspecified"))
      (node (ref "U2") (pin "6") (pinfunction "6_6") (pintype "unspecified"))
      (node (ref "U6") (pin "23") (pinfunction "23_23") (pintype "unspecified"))
      (node (ref "U6") (pin "6") (pinfunction "6_6") (pintype "unspecified"))
    )
    (net (code "74") (name "X11_2") (class "Default")
      (node (ref "M2") (pin "8") (pinfunction "X11_8") (pintype "unspecified"))
      (node (ref "U8") (pin "10") (pinfunction "10_10") (pintype "unspecified"))
      (node (ref "U8") (pin "19") (pinfunction "19_19") (pintype "unspecified"))
      (node (ref "U9") (pin "10") (pinfunction "10_10") (pintype "unspecified"))
      (node (ref "U9") (pin "19") (pinfunction "19_19") (pintype "unspecified"))
    )
    (net (code "75") (name "X12_1") (class "Default")
      (node (ref "M1") (pin "25") (pinfunction "X12_25") (pintype "unspecified"))
      (node (ref "U2") (pin "22") (pinfunction "22_22") (pintype "unspecified"))
      (node (ref "U2") (pin "7") (pinfunction "7_7") (pintype "unspecified"))
      (node (ref "U6") (pin "22") (pinfunction "22_22") (pintype "unspecified"))
      (node (ref "U6") (pin "7") (pinfunction "7_7") (pintype "unspecified"))
    )
    (net (code "76") (name "X12_2") (class "Default")
      (node (ref "M2") (pin "25") (pinfunction "X12_25") (pintype "unspecified"))
      (node (ref "U8") (pin "11") (pinfunction "11_11") (pintype "unspecified"))
      (node (ref "U8") (pin "18") (pinfunction "18_18") (pintype "unspecified"))
      (node (ref "U9") (pin "11") (pinfunction "11_11") (pintype "unspecified"))
      (node (ref "U9") (pin "18") (pinfunction "18_18") (pintype "unspecified"))
    )
    (net (code "77") (name "X13_1") (class "Default")
      (node (ref "M1") (pin "24") (pinfunction "X13_24") (pintype "unspecified"))
      (node (ref "U2") (pin "21") (pinfunction "21_21") (pintype "unspecified"))
      (node (ref "U2") (pin "8") (pinfunction "8_8") (pintype "unspecified"))
      (node (ref "U6") (pin "21") (pinfunction "21_21") (pintype "unspecified"))
      (node (ref "U6") (pin "8") (pinfunction "8_8") (pintype "unspecified"))
    )
    (net (code "78") (name "X13_2") (class "Default")
      (node (ref "M2") (pin "24") (pinfunction "X13_24") (pintype "unspecified"))
      (node (ref "U8") (pin "12") (pinfunction "12_12") (pintype "unspecified"))
      (node (ref "U8") (pin "17") (pinfunction "17_17") (pintype "unspecified"))
      (node (ref "U9") (pin "12") (pinfunction "12_12") (pintype "unspecified"))
      (node (ref "U9") (pin "17") (pinfunction "17_17") (pintype "unspecified"))
    )
    (net (code "79") (name "X14_1") (class "Default")
      (node (ref "M1") (pin "1") (pinfunction "X14_1") (pintype "unspecified"))
      (node (ref "U2") (pin "20") (pinfunction "20_20") (pintype "unspecified"))
      (node (ref "U2") (pin "9") (pinfunction "9_9") (pintype "unspecified"))
      (node (ref "U6") (pin "20") (pinfunction "20_20") (pintype "unspecified"))
      (node (ref "U6") (pin "9") (pinfunction "9_9") (pintype "unspecified"))
    )
    (net (code "80") (name "X14_2") (class "Default")
      (node (ref "M2") (pin "1") (pinfunction "X14_1") (pintype "unspecified"))
      (node (ref "U8") (pin "13") (pinfunction "13_13") (pintype "unspecified"))
      (node (ref "U8") (pin "16") (pinfunction "16_16") (pintype "unspecified"))
      (node (ref "U9") (pin "13") (pinfunction "13_13") (pintype "unspecified"))
      (node (ref "U9") (pin "16") (pinfunction "16_16") (pintype "unspecified"))
    )
    (net (code "81") (name "X15_1") (class "Default")
      (node (ref "M1") (pin "2") (pinfunction "X15_2") (pintype "unspecified"))
      (node (ref "U2") (pin "10") (pinfunction "10_10") (pintype "unspecified"))
      (node (ref "U2") (pin "19") (pinfunction "19_19") (pintype "unspecified"))
      (node (ref "U6") (pin "10") (pinfunction "10_10") (pintype "unspecified"))
      (node (ref "U6") (pin "19") (pinfunction "19_19") (pintype "unspecified"))
    )
    (net (code "82") (name "X15_2") (class "Default")
      (node (ref "M2") (pin "2") (pinfunction "X15_2") (pintype "unspecified"))
    )
    (net (code "83") (name "X15_4") (class "Default")
      (node (ref "U8") (pin "14") (pinfunction "14_14") (pintype "unspecified"))
      (node (ref "U8") (pin "15") (pinfunction "15_15") (pintype "unspecified"))
      (node (ref "U9") (pin "14") (pinfunction "14_14") (pintype "unspecified"))
      (node (ref "U9") (pin "15") (pinfunction "15_15") (pintype "unspecified"))
    )
    (net (code "84") (name "Y0") (class "Default")
      (node (ref "U3") (pin "15") (pinfunction "Y0_15") (pintype "unspecified"))
      (node (ref "U7") (pin "1") (pinfunction "1A_1") (pintype "unspecified"))
    )
    (net (code "85") (name "Y0_1") (class "Default")
      (node (ref "M1") (pin "33") (pinfunction "Y0_33") (pintype "unspecified"))
      (node (ref "U4") (pin "1") (pinfunction "(PCINT5/RESET#/ADC0/dW)PB5_1") (pintype "unspecified"))
    )
    (net (code "86") (name "Y1") (class "Default")
      (node (ref "U3") (pin "14") (pinfunction "Y1_14") (pintype "unspecified"))
      (node (ref "U7") (pin "3") (pinfunction "2A_3") (pintype "unspecified"))
    )
    (net (code "87") (name "Y1_1") (class "Default")
      (node (ref "M1") (pin "35") (pinfunction "Y1_35") (pintype "unspecified"))
      (node (ref "U4") (pin "2") (pinfunction "(PCINT3/XTAL1/CLKI/OC1B#/ADC3)PB3_2") (pintype "unspecified"))
    )
    (net (code "88") (name "Y2_1") (class "Default")
      (node (ref "M1") (pin "37") (pinfunction "Y2_37") (pintype "unspecified"))
      (node (ref "U4") (pin "3") (pinfunction "(PCINT4/XTAL2/CLKO/OC1B/ADC2)PB4_3") (pintype "unspecified"))
    )
    (net (code "89") (name "Y3_1") (class "Default")
      (node (ref "C_LED_1") (pin "2") (pinfunction "2_2") (pintype "unspecified"))
      (node (ref "C_LED_10") (pin "2") (pinfunction "2_2") (pintype "unspecified"))
      (node (ref "C_LED_13") (pin "2") (pinfunction "2_2") (pintype "unspecified"))
      (node (ref "C_LED_16") (pin "2") (pinfunction "2_2") (pintype "unspecified"))
      (node (ref "C_LED_19") (pin "2") (pinfunction "2_2") (pintype "unspecified"))
      (node (ref "C_LED_22") (pin "2") (pinfunction "2_2") (pintype "unspecified"))
      (node (ref "C_LED_26") (pin "2") (pinfunction "2_2") (pintype "unspecified"))
      (node (ref "C_LED_29") (pin "2") (pinfunction "2_2") (pintype "unspecified"))
      (node (ref "C_LED_31") (pin "2") (pinfunction "2_2") (pintype "unspecified"))
      (node (ref "C_LED_4") (pin "2") (pinfunction "2_2") (pintype "unspecified"))
      (node (ref "C_LED_7") (pin "2") (pinfunction "2_2") (pintype "unspecified"))
      (node (ref "LED1") (pin "3") (pinfunction "GND_3") (pintype "unspecified"))
      (node (ref "LED10") (pin "3") (pinfunction "GND_3") (pintype "unspecified"))
      (node (ref "LED11") (pin "3") (pinfunction "GND_3") (pintype "unspecified"))
      (node (ref "LED12") (pin "3") (pinfunction "GND_3") (pintype "unspecified"))
      (node (ref "LED13") (pin "3") (pinfunction "GND_3") (pintype "unspecified"))
      (node (ref "LED14") (pin "3") (pinfunction "GND_3") (pintype "unspecified"))
      (node (ref "LED15") (pin "3") (pinfunction "GND_3") (pintype "unspecified"))
      (node (ref "LED16") (pin "3") (pinfunction "GND_3") (pintype "unspecified"))
      (node (ref "LED17") (pin "3") (pinfunction "GND_3") (pintype "unspecified"))
      (node (ref "LED18") (pin "3") (pinfunction "GND_3") (pintype "unspecified"))
      (node (ref "LED19") (pin "3") (pinfunction "GND_3") (pintype "unspecified"))
      (node (ref "LED2") (pin "3") (pinfunction "GND_3") (pintype "unspecified"))
      (node (ref "LED20") (pin "3") (pinfunction "GND_3") (pintype "unspecified"))
      (node (ref "LED21") (pin "3") (pinfunction "GND_3") (pintype "unspecified"))
      (node (ref "LED22") (pin "3") (pinfunction "GND_3") (pintype "unspecified"))
      (node (ref "LED23") (pin "3") (pinfunction "GND_3") (pintype "unspecified"))
      (node (ref "LED24") (pin "3") (pinfunction "GND_3") (pintype "unspecified"))
      (node (ref "LED25") (pin "3") (pinfunction "GND_3") (pintype "unspecified"))
      (node (ref "LED26") (pin "3") (pinfunction "GND_3") (pintype "unspecified"))
      (node (ref "LED27") (pin "3") (pinfunction "GND_3") (pintype "unspecified"))
      (node (ref "LED28") (pin "3") (pinfunction "GND_3") (pintype "unspecified"))
      (node (ref "LED29") (pin "3") (pinfunction "GND_3") (pintype "unspecified"))
      (node (ref "LED3") (pin "3") (pinfunction "GND_3") (pintype "unspecified"))
      (node (ref "LED30") (pin "3") (pinfunction "GND_3") (pintype "unspecified"))
      (node (ref "LED31") (pin "3") (pinfunction "GND_3") (pintype "unspecified"))
      (node (ref "LED32") (pin "3") (pinfunction "GND_3") (pintype "unspecified"))
      (node (ref "LED4") (pin "3") (pinfunction "GND_3") (pintype "unspecified"))
      (node (ref "LED5") (pin "3") (pinfunction "GND_3") (pintype "unspecified"))
      (node (ref "LED6") (pin "3") (pinfunction "GND_3") (pintype "unspecified"))
      (node (ref "LED7") (pin "3") (pinfunction "GND_3") (pintype "unspecified"))
      (node (ref "LED8") (pin "3") (pinfunction "GND_3") (pintype "unspecified"))
      (node (ref "LED9") (pin "3") (pinfunction "GND_3") (pintype "unspecified"))
      (node (ref "M1") (pin "12") (pinfunction "GND_12") (pintype "unspecified"))
      (node (ref "M1") (pin "16") (pinfunction "VEE_16") (pintype "unspecified"))
      (node (ref "M1") (pin "39") (pinfunction "Y3_39") (pintype "unspecified"))
      (node (ref "M2") (pin "12") (pinfunction "GND_12") (pintype "unspecified"))
      (node (ref "M2") (pin "16") (pinfunction "VEE_16") (pintype "unspecified"))
      (node (ref "U1") (pin "4") (pinfunction "GND_4") (pintype "unspecified"))
      (node (ref "U3") (pin "4") (pinfunction "G#2A_4") (pintype "unspecified"))
      (node (ref "U3") (pin "5") (pinfunction "G#2B_5") (pintype "unspecified"))
      (node (ref "U3") (pin "8") (pinfunction "GND_8") (pintype "unspecified"))
      (node (ref "U4") (pin "4") (pinfunction "GND_4") (pintype "unspecified"))
      (node (ref "U7") (pin "7") (pinfunction "GND_7") (pintype "unspecified"))
    )
    (net (code "90") (name "Y4_1") (class "Default")
      (node (ref "M1") (pin "17") (pinfunction "Y4_17") (pintype "unspecified"))
      (node (ref "U4") (pin "5") (pinfunction "PB0(MOSI/DI/SDA/AIN0/OC0A/OC1A#/AREF/PCINT0)_5") (pintype "unspecified"))
    )
    (net (code "91") (name "Y5_1") (class "Default")
      (node (ref "M1") (pin "15") (pinfunction "Y5_15") (pintype "unspecified"))
      (node (ref "U4") (pin "6") (pinfunction "PB1(MISO/DO/AIN1/OC0B/OC1A/PCINT1)_6") (pintype "unspecified"))
    )
    (net (code "92") (name "Y6_1") (class "Default")
      (node (ref "M1") (pin "13") (pinfunction "Y6_13") (pintype "unspecified"))
      (node (ref "U4") (pin "7") (pinfunction "PB2(SCK/USCK/SCL/ADC1/T0/INT0/PCINT2)_7") (pintype "unspecified"))
    )
    (net (code "93") (name "Y7_1") (class "Default")
      (node (ref "C_LED_1") (pin "1") (pinfunction "1_1") (pintype "unspecified"))
      (node (ref "C_LED_10") (pin "1") (pinfunction "1_1") (pintype "unspecified"))
      (node (ref "C_LED_13") (pin "1") (pinfunction "1_1") (pintype "unspecified"))
      (node (ref "C_LED_16") (pin "1") (pinfunction "1_1") (pintype "unspecified"))
      (node (ref "C_LED_19") (pin "1") (pinfunction "1_1") (pintype "unspecified"))
      (node (ref "C_LED_22") (pin "1") (pinfunction "1_1") (pintype "unspecified"))
      (node (ref "C_LED_26") (pin "1") (pinfunction "1_1") (pintype "unspecified"))
      (node (ref "C_LED_29") (pin "1") (pinfunction "1_1") (pintype "unspecified"))
      (node (ref "C_LED_31") (pin "1") (pinfunction "1_1") (pintype "unspecified"))
      (node (ref "C_LED_4") (pin "1") (pinfunction "1_1") (pintype "unspecified"))
      (node (ref "C_LED_7") (pin "1") (pinfunction "1_1") (pintype "unspecified"))
      (node (ref "LED1") (pin "2") (pinfunction "VDD_2") (pintype "unspecified"))
      (node (ref "LED10") (pin "2") (pinfunction "VDD_2") (pintype "unspecified"))
      (node (ref "LED11") (pin "2") (pinfunction "VDD_2") (pintype "unspecified"))
      (node (ref "LED12") (pin "2") (pinfunction "VDD_2") (pintype "unspecified"))
      (node (ref "LED13") (pin "2") (pinfunction "VDD_2") (pintype "unspecified"))
      (node (ref "LED14") (pin "2") (pinfunction "VDD_2") (pintype "unspecified"))
      (node (ref "LED15") (pin "2") (pinfunction "VDD_2") (pintype "unspecified"))
      (node (ref "LED16") (pin "2") (pinfunction "VDD_2") (pintype "unspecified"))
      (node (ref "LED17") (pin "2") (pinfunction "VDD_2") (pintype "unspecified"))
      (node (ref "LED18") (pin "2") (pinfunction "VDD_2") (pintype "unspecified"))
      (node (ref "LED19") (pin "2") (pinfunction "VDD_2") (pintype "unspecified"))
      (node (ref "LED2") (pin "2") (pinfunction "VDD_2") (pintype "unspecified"))
      (node (ref "LED20") (pin "2") (pinfunction "VDD_2") (pintype "unspecified"))
      (node (ref "LED21") (pin "2") (pinfunction "VDD_2") (pintype "unspecified"))
      (node (ref "LED22") (pin "2") (pinfunction "VDD_2") (pintype "unspecified"))
      (node (ref "LED23") (pin "2") (pinfunction "VDD_2") (pintype "unspecified"))
      (node (ref "LED24") (pin "2") (pinfunction "VDD_2") (pintype "unspecified"))
      (node (ref "LED25") (pin "2") (pinfunction "VDD_2") (pintype "unspecified"))
      (node (ref "LED26") (pin "2") (pinfunction "VDD_2") (pintype "unspecified"))
      (node (ref "LED27") (pin "2") (pinfunction "VDD_2") (pintype "unspecified"))
      (node (ref "LED28") (pin "2") (pinfunction "VDD_2") (pintype "unspecified"))
      (node (ref "LED29") (pin "2") (pinfunction "VDD_2") (pintype "unspecified"))
      (node (ref "LED3") (pin "2") (pinfunction "VDD_2") (pintype "unspecified"))
      (node (ref "LED30") (pin "2") (pinfunction "VDD_2") (pintype "unspecified"))
      (node (ref "LED31") (pin "2") (pinfunction "VDD_2") (pintype "unspecified"))
      (node (ref "LED32") (pin "2") (pinfunction "VDD_2") (pintype "unspecified"))
      (node (ref "LED4") (pin "2") (pinfunction "VDD_2") (pintype "unspecified"))
      (node (ref "LED5") (pin "2") (pinfunction "VDD_2") (pintype "unspecified"))
      (node (ref "LED6") (pin "2") (pinfunction "VDD_2") (pintype "unspecified"))
      (node (ref "LED7") (pin "2") (pinfunction "VDD_2") (pintype "unspecified"))
      (node (ref "LED8") (pin "2") (pinfunction "VDD_2") (pintype "unspecified"))
      (node (ref "LED9") (pin "2") (pinfunction "VDD_2") (pintype "unspecified"))
      (node (ref "M1") (pin "10") (pinfunction "P/-S_10") (pintype "unspecified"))
      (node (ref "M1") (pin "11") (pinfunction "Y7_11") (pintype "unspecified"))
      (node (ref "M1") (pin "38") (pinfunction "VDD_38") (pintype "unspecified"))
      (node (ref "M2") (pin "10") (pinfunction "P/-S_10") (pintype "unspecified"))
      (node (ref "M2") (pin "38") (pinfunction "VDD_38") (pintype "unspecified"))
      (node (ref "U1") (pin "27") (pinfunction "+5V_27") (pintype "unspecified"))
      (node (ref "U3") (pin "16") (pinfunction "VCC_16") (pintype "unspecified"))
      (node (ref "U4") (pin "8") (pinfunction "VCC_8") (pintype "unspecified"))
      (node (ref "U7") (pin "14") (pinfunction "VCC_14") (pintype "unspecified"))
    )
    (net (code "94") (name "unconnected-(LED24-DO-Pad1)") (class "Default")
      (node (ref "LED24") (pin "1") (pinfunction "DO_1") (pintype "unspecified"))
    )
    (net (code "95") (name "unconnected-(LED25-DO-Pad1)") (class "Default")
      (node (ref "LED25") (pin "1") (pinfunction "DO_1") (pintype "unspecified"))
    )
    (net (code "96") (name "unconnected-(M1-NC-Pad9)") (class "Default")
      (node (ref "M1") (pin "9") (pinfunction "NC_9") (pintype "unspecified"))
    )
    (net (code "97") (name "unconnected-(M1-NC-Pad22)") (class "Default")
      (node (ref "M1") (pin "22") (pinfunction "NC_22") (pintype "unspecified"))
    )
    (net (code "98") (name "unconnected-(M1-NC-Pad23)") (class "Default")
      (node (ref "M1") (pin "23") (pinfunction "NC_23") (pintype "unspecified"))
    )
    (net (code "99") (name "unconnected-(M1-NC-Pad32)") (class "Default")
      (node (ref "M1") (pin "32") (pinfunction "NC_32") (pintype "unspecified"))
    )
    (net (code "100") (name "unconnected-(M1-NC-Pad44)") (class "Default")
      (node (ref "M1") (pin "44") (pinfunction "NC_44") (pintype "unspecified"))
    )
    (net (code "101") (name "unconnected-(M2-NC-Pad9)") (class "Default")
      (node (ref "M2") (pin "9") (pinfunction "NC_9") (pintype "unspecified"))
    )
    (net (code "102") (name "unconnected-(M2-NC-Pad22)") (class "Default")
      (node (ref "M2") (pin "22") (pinfunction "NC_22") (pintype "unspecified"))
    )
    (net (code "103") (name "unconnected-(M2-NC-Pad23)") (class "Default")
      (node (ref "M2") (pin "23") (pinfunction "NC_23") (pintype "unspecified"))
    )
    (net (code "104") (name "unconnected-(M2-NC-Pad32)") (class "Default")
      (node (ref "M2") (pin "32") (pinfunction "NC_32") (pintype "unspecified"))
    )
    (net (code "105") (name "unconnected-(M2-NC-Pad44)") (class "Default")
      (node (ref "M2") (pin "44") (pinfunction "NC_44") (pintype "unspecified"))
    )
    (net (code "106") (name "unconnected-(U1-A4-Pad23)") (class "Default")
      (node (ref "U1") (pin "23") (pinfunction "A4_23") (pintype "unspecified"))
    )
    (net (code "107") (name "unconnected-(U1-A5-Pad24)") (class "Default")
      (node (ref "U1") (pin "24") (pinfunction "A5_24") (pintype "unspecified"))
    )
    (net (code "108") (name "unconnected-(U1-A6-Pad25)") (class "Default")
      (node (ref "U1") (pin "25") (pinfunction "A6_25") (pintype "unspecified"))
    )
    (net (code "109") (name "unconnected-(U1-A7-Pad26)") (class "Default")
      (node (ref "U1") (pin "26") (pinfunction "A7_26") (pintype "unspecified"))
    )
    (net (code "110") (name "unconnected-(U1-AREF-Pad18)") (class "Default")
      (node (ref "U1") (pin "18") (pinfunction "AREF_18") (pintype "unspecified"))
    )
    (net (code "111") (name "unconnected-(U1-D0{slash}RX-Pad2)") (class "Default")
      (node (ref "U1") (pin "2") (pinfunction "D0/RX_2") (pintype "unspecified"))
    )
    (net (code "112") (name "unconnected-(U1-D1{slash}TX-Pad1)") (class "Default")
      (node (ref "U1") (pin "1") (pinfunction "D1/TX_1") (pintype "unspecified"))
    )
    (net (code "113") (name "unconnected-(U1-D13-Pad16)") (class "Default")
      (node (ref "U1") (pin "16") (pinfunction "D13_16") (pintype "unspecified"))
    )
    (net (code "114") (name "unconnected-(U1-GND-Pad29)") (class "Default")
      (node (ref "U1") (pin "29") (pinfunction "GND_29") (pintype "unspecified"))
    )
    (net (code "115") (name "unconnected-(U1-RESET-Pad3)") (class "Default")
      (node (ref "U1") (pin "3") (pinfunction "RESET_3") (pintype "unspecified"))
    )
    (net (code "116") (name "unconnected-(U1-VIN-Pad30)") (class "Default")
      (node (ref "U1") (pin "30") (pinfunction "VIN_30") (pintype "unspecified"))
    )
    (net (code "117") (name "unconnected-(U2-Pad1)") (class "Default")
      (node (ref "U2") (pin "1") (pinfunction "1_1") (pintype "unspecified"))
    )
    (net (code "118") (name "unconnected-(U2-Pad2)") (class "Default")
      (node (ref "U2") (pin "2") (pinfunction "2_2") (pintype "unspecified"))
    )
    (net (code "119") (name "unconnected-(U2-Pad27)") (class "Default")
      (node (ref "U2") (pin "27") (pinfunction "27_27") (pintype "unspecified"))
    )
    (net (code "120") (name "unconnected-(U2-Pad28)") (class "Default")
      (node (ref "U2") (pin "28") (pinfunction "28_28") (pintype "unspecified"))
    )
    (net (code "121") (name "unconnected-(U3-Y2-Pad13)") (class "Default")
      (node (ref "U3") (pin "13") (pinfunction "Y2_13") (pintype "unspecified"))
    )
    (net (code "122") (name "unconnected-(U3-Y3-Pad12)") (class "Default")
      (node (ref "U3") (pin "12") (pinfunction "Y3_12") (pintype "unspecified"))
    )
    (net (code "123") (name "unconnected-(U3-Y4-Pad11)") (class "Default")
      (node (ref "U3") (pin "11") (pinfunction "Y4_11") (pintype "unspecified"))
    )
    (net (code "124") (name "unconnected-(U3-Y5-Pad10)") (class "Default")
      (node (ref "U3") (pin "10") (pinfunction "Y5_10") (pintype "unspecified"))
    )
    (net (code "125") (name "unconnected-(U3-Y6-Pad9)") (class "Default")
      (node (ref "U3") (pin "9") (pinfunction "Y6_9") (pintype "unspecified"))
    )
    (net (code "126") (name "unconnected-(U3-Y7-Pad7)") (class "Default")
      (node (ref "U3") (pin "7") (pinfunction "Y7_7") (pintype "unspecified"))
    )
    (net (code "127") (name "unconnected-(U6-Pad1)") (class "Default")
      (node (ref "U6") (pin "1") (pinfunction "1_1") (pintype "unspecified"))
    )
    (net (code "128") (name "unconnected-(U6-Pad2)") (class "Default")
      (node (ref "U6") (pin "2") (pinfunction "2_2") (pintype "unspecified"))
    )
    (net (code "129") (name "unconnected-(U6-Pad27)") (class "Default")
      (node (ref "U6") (pin "27") (pinfunction "27_27") (pintype "unspecified"))
    )
    (net (code "130") (name "unconnected-(U6-Pad28)") (class "Default")
      (node (ref "U6") (pin "28") (pinfunction "28_28") (pintype "unspecified"))
    )
    (net (code "131") (name "unconnected-(U7-4A-Pad9)") (class "Default")
      (node (ref "U7") (pin "9") (pinfunction "4A_9") (pintype "unspecified"))
    )
    (net (code "132") (name "unconnected-(U7-4Y#-Pad8)") (class "Default")
      (node (ref "U7") (pin "8") (pinfunction "4Y#_8") (pintype "unspecified"))
    )
    (net (code "133") (name "unconnected-(U7-5A-Pad11)") (class "Default")
      (node (ref "U7") (pin "11") (pinfunction "5A_11") (pintype "unspecified"))
    )
    (net (code "134") (name "unconnected-(U7-5Y#-Pad10)") (class "Default")
      (node (ref "U7") (pin "10") (pinfunction "5Y#_10") (pintype "unspecified"))
    )
    (net (code "135") (name "unconnected-(U7-6A-Pad13)") (class "Default")
      (node (ref "U7") (pin "13") (pinfunction "6A_13") (pintype "unspecified"))
    )
    (net (code "136") (name "unconnected-(U7-6Y#-Pad12)") (class "Default")
      (node (ref "U7") (pin "12") (pinfunction "6Y#_12") (pintype "unspecified"))
    )
    (net (code "137") (name "unconnected-(U8-Pad1)") (class "Default")
      (node (ref "U8") (pin "1") (pinfunction "1_1") (pintype "unspecified"))
    )
    (net (code "138") (name "unconnected-(U8-Pad2)") (class "Default")
      (node (ref "U8") (pin "2") (pinfunction "2_2") (pintype "unspecified"))
    )
    (net (code "139") (name "unconnected-(U8-Pad27)") (class "Default")
      (node (ref "U8") (pin "27") (pinfunction "27_27") (pintype "unspecified"))
    )
    (net (code "140") (name "unconnected-(U8-Pad28)") (class "Default")
      (node (ref "U8") (pin "28") (pinfunction "28_28") (pintype "unspecified"))
    )
    (net (code "141") (name "unconnected-(U9-Pad1)") (class "Default")
      (node (ref "U9") (pin "1") (pinfunction "1_1") (pintype "unspecified"))
    )
    (net (code "142") (name "unconnected-(U9-Pad2)") (class "Default")
      (node (ref "U9") (pin "2") (pinfunction "2_2") (pintype "unspecified"))
    )
    (net (code "143") (name "unconnected-(U9-Pad27)") (class "Default")
      (node (ref "U9") (pin "27") (pinfunction "27_27") (pintype "unspecified"))
    )
    (net (code "144") (name "unconnected-(U9-Pad28)") (class "Default")
      (node (ref "U9") (pin "28") (pinfunction "28_28") (pintype "unspecified"))
    )
    (net (code "145") (name "unconnected-(U10-Pad1)") (class "Default")
      (node (ref "U10") (pin "1") (pinfunction "1_1") (pintype "unspecified"))
    )
    (net (code "146") (name "unconnected-(U10-Pad2)") (class "Default")
      (node (ref "U10") (pin "2") (pinfunction "2_2") (pintype "unspecified"))
    )
    (net (code "147") (name "unconnected-(U10-Pad3)") (class "Default")
      (node (ref "U10") (pin "3") (pinfunction "3_3") (pintype "unspecified"))
    )
    (net (code "148") (name "unconnected-(U10-Pad4)") (class "Default")
      (node (ref "U10") (pin "4") (pinfunction "4_4") (pintype "unspecified"))
    )
    (net (code "149") (name "unconnected-(U10-Pad5)") (class "Default")
      (node (ref "U10") (pin "5") (pinfunction "5_5") (pintype "unspecified"))
    )
    (net (code "150") (name "unconnected-(U10-Pad6)") (class "Default")
      (node (ref "U10") (pin "6") (pinfunction "6_6") (pintype "unspecified"))
    )
    (net (code "151") (name "unconnected-(U10-Pad7)") (class "Default")
      (node (ref "U10") (pin "7") (pinfunction "7_7") (pintype "unspecified"))
    )
    (net (code "152") (name "unconnected-(U10-Pad8)") (class "Default")
      (node (ref "U10") (pin "8") (pinfunction "8_8") (pintype "unspecified"))
    )
    (net (code "153") (name "unconnected-(U10-Pad9)") (class "Default")
      (node (ref "U10") (pin "9") (pinfunction "9_9") (pintype "unspecified"))
    )
    (net (code "154") (name "unconnected-(U10-Pad10)") (class "Default")
      (node (ref "U10") (pin "10") (pinfunction "10_10") (pintype "unspecified"))
    )
    (net (code "155") (name "unconnected-(U10-Pad11)") (class "Default")
      (node (ref "U10") (pin "11") (pinfunction "11_11") (pintype "unspecified"))
    )
    (net (code "156") (name "unconnected-(U10-Pad12)") (class "Default")
      (node (ref "U10") (pin "12") (pinfunction "12_12") (pintype "unspecified"))
    )
    (net (code "157") (name "unconnected-(U10-Pad13)") (class "Default")
      (node (ref "U10") (pin "13") (pinfunction "13_13") (pintype "unspecified"))
    )
    (net (code "158") (name "unconnected-(U10-Pad14)") (class "Default")
      (node (ref "U10") (pin "14") (pinfunction "14_14") (pintype "unspecified"))
    )
    (net (code "159") (name "unconnected-(U10-Pad15)") (class "Default")
      (node (ref "U10") (pin "15") (pinfunction "15_15") (pintype "unspecified"))
    )
    (net (code "160") (name "unconnected-(U10-Pad16)") (class "Default")
      (node (ref "U10") (pin "16") (pinfunction "16_16") (pintype "unspecified"))
    )
    (net (code "161") (name "unconnected-(U10-Pad17)") (class "Default")
      (node (ref "U10") (pin "17") (pinfunction "17_17") (pintype "unspecified"))
    )
    (net (code "162") (name "unconnected-(U10-Pad18)") (class "Default")
      (node (ref "U10") (pin "18") (pinfunction "18_18") (pintype "unspecified"))
    )
    (net (code "163") (name "unconnected-(U10-Pad19)") (class "Default")
      (node (ref "U10") (pin "19") (pinfunction "19_19") (pintype "unspecified"))
    )
    (net (code "164") (name "unconnected-(U10-Pad20)") (class "Default")
      (node (ref "U10") (pin "20") (pinfunction "20_20") (pintype "unspecified"))
    )
    (net (code "165") (name "unconnected-(U10-Pad21)") (class "Default")
      (node (ref "U10") (pin "21") (pinfunction "21_21") (pintype "unspecified"))
    )
    (net (code "166") (name "unconnected-(U10-Pad22)") (class "Default")
      (node (ref "U10") (pin "22") (pinfunction "22_22") (pintype "unspecified"))
    )
    (net (code "167") (name "unconnected-(U10-Pad23)") (class "Default")
      (node (ref "U10") (pin "23") (pinfunction "23_23") (pintype "unspecified"))
    )
    (net (code "168") (name "unconnected-(U10-Pad24)") (class "Default")
      (node (ref "U10") (pin "24") (pinfunction "24_24") (pintype "unspecified"))
    )
    (net (code "169") (name "unconnected-(U10-Pad25)") (class "Default")
      (node (ref "U10") (pin "25") (pinfunction "25_25") (pintype "unspecified"))
    )
    (net (code "170") (name "unconnected-(U10-Pad26)") (class "Default")
      (node (ref "U10") (pin "26") (pinfunction "26_26") (pintype "unspecified"))
    )
    (net (code "171") (name "unconnected-(U10-Pad27)") (class "Default")
      (node (ref "U10") (pin "27") (pinfunction "27_27") (pintype "unspecified"))
    )
    (net (code "172") (name "unconnected-(U10-Pad28)") (class "Default")
      (node (ref "U10") (pin "28") (pinfunction "28_28") (pintype "unspecified"))
    )
  )
)
